# mod_panel_voltage.net
KiCad netlist of a schematic drawn in EAGLE
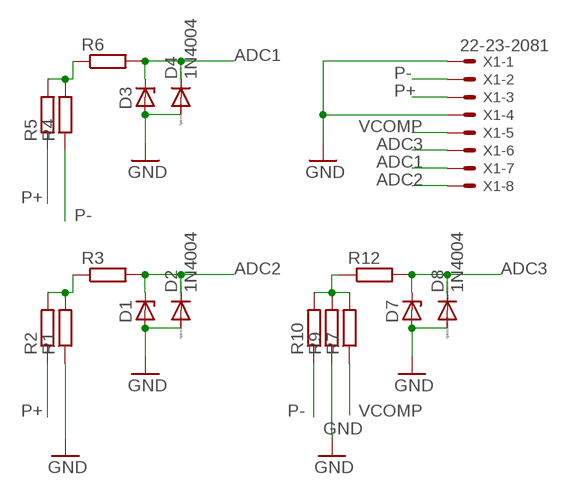
[diagram p0: schematic, sheet 1]

(export (version "E")
  (design (tool "Eeschema 10.0.6"))
  (components
    (comp (ref "D1")
      (value "ZENER-DIODEDO34-7")
      (footprint "eagle-import:DO34Z7")
      (libsource (lib "eagle-import") (part "ZENER-DIODEDO34-7"))
    )
    (comp (ref "D2")
      (value "1N4004")
      (footprint "eagle-import:DO41-10")
      (libsource (lib "eagle-import") (part "1N4004"))
    )
    (comp (ref "D3")
      (value "ZENER-DIODEDO34-7")
      (footprint "eagle-import:DO34Z7")
      (libsource (lib "eagle-import") (part "ZENER-DIODEDO34-7"))
    )
    (comp (ref "D4")
      (value "1N4004")
      (footprint "eagle-import:DO41-10")
      (libsource (lib "eagle-import") (part "1N4004"))
    )
    (comp (ref "D7")
      (value "ZENER-DIODEDO34-7")
      (footprint "eagle-import:DO34Z7")
      (libsource (lib "eagle-import") (part "ZENER-DIODEDO34-7"))
    )
    (comp (ref "D8")
      (value "1N4004")
      (footprint "eagle-import:DO41-10")
      (libsource (lib "eagle-import") (part "1N4004"))
    )
    (comp (ref "R1")
      (value "R-EU_0204/5")
      (footprint "eagle-import:0204_5")
      (libsource (lib "eagle-import") (part "R-EU_0204/5"))
    )
    (comp (ref "R2")
      (value "R-EU_0204/5")
      (footprint "eagle-import:0204_5")
      (libsource (lib "eagle-import") (part "R-EU_0204/5"))
    )
    (comp (ref "R3")
      (value "R-EU_0204/5")
      (footprint "eagle-import:0204_5")
      (libsource (lib "eagle-import") (part "R-EU_0204/5"))
    )
    (comp (ref "R4")
      (value "R-EU_0204/5")
      (footprint "eagle-import:0204_5")
      (libsource (lib "eagle-import") (part "R-EU_0204/5"))
    )
    (comp (ref "R5")
      (value "R-EU_0204/5")
      (footprint "eagle-import:0204_5")
      (libsource (lib "eagle-import") (part "R-EU_0204/5"))
    )
    (comp (ref "R6")
      (value "R-EU_0204/5")
      (footprint "eagle-import:0204_5")
      (libsource (lib "eagle-import") (part "R-EU_0204/5"))
    )
    (comp (ref "R7")
      (value "R-EU_0204/5")
      (footprint "eagle-import:0204_5")
      (libsource (lib "eagle-import") (part "R-EU_0204/5"))
    )
    (comp (ref "R9")
      (value "R-EU_0204/5")
      (footprint "eagle-import:0204_5")
      (libsource (lib "eagle-import") (part "R-EU_0204/5"))
    )
    (comp (ref "R10")
      (value "R-EU_0204/5")
      (footprint "eagle-import:0204_5")
      (libsource (lib "eagle-import") (part "R-EU_0204/5"))
    )
    (comp (ref "R12")
      (value "R-EU_0204/5")
      (footprint "eagle-import:0204_5")
      (libsource (lib "eagle-import") (part "R-EU_0204/5"))
    )
    (comp (ref "X1")
      (value "22-23-2081")
      (footprint "eagle-import:22-23-2081")
      (fields (field (name "MF") "MOLEX"))
      (libsource (lib "eagle-import") (part "22-23-2081"))
    )
  )
  (nets
    (net (code "1") (name "/ADC1") (class "Default")
      (node (ref "D3") (pin "C") (pinfunction "C_C") (pintype "passive"))
      (node (ref "D4") (pin "C") (pinfunction "C_C") (pintype "passive"))
      (node (ref "R6") (pin "2") (pinfunction "2_2") (pintype "passive"))
      (node (ref "X1") (pin "7") (pinfunction "S_7") (pintype "passive"))
    )
    (net (code "2") (name "/ADC2") (class "Default")
      (node (ref "D1") (pin "C") (pinfunction "C_C") (pintype "passive"))
      (node (ref "D2") (pin "C") (pinfunction "C_C") (pintype "passive"))
      (node (ref "R3") (pin "2") (pinfunction "2_2") (pintype "passive"))
      (node (ref "X1") (pin "8") (pinfunction "S_8") (pintype "passive"))
    )
    (net (code "3") (name "/ADC3") (class "Default")
      (node (ref "D7") (pin "C") (pinfunction "C_C") (pintype "passive"))
      (node (ref "D8") (pin "C") (pinfunction "C_C") (pintype "passive"))
      (node (ref "R12") (pin "2") (pinfunction "2_2") (pintype "passive"))
      (node (ref "X1") (pin "6") (pinfunction "S_6") (pintype "passive"))
    )
    (net (code "4") (name "/P+") (class "Default")
      (node (ref "R2") (pin "1") (pinfunction "1_1") (pintype "passive"))
      (node (ref "R5") (pin "1") (pinfunction "1_1") (pintype "passive"))
      (node (ref "X1") (pin "3") (pinfunction "S_3") (pintype "passive"))
    )
    (net (code "5") (name "/P-") (class "Default")
      (node (ref "R10") (pin "1") (pinfunction "1_1") (pintype "passive"))
      (node (ref "R4") (pin "1") (pinfunction "1_1") (pintype "passive"))
      (node (ref "X1") (pin "2") (pinfunction "S_2") (pintype "passive"))
    )
    (net (code "6") (name "/VCOMP") (class "Default")
      (node (ref "R7") (pin "1") (pinfunction "1_1") (pintype "passive"))
      (node (ref "X1") (pin "5") (pinfunction "S_5") (pintype "passive"))
    )
    (net (code "7") (name "GND") (class "Default")
      (node (ref "D1") (pin "A") (pinfunction "A_A") (pintype "passive"))
      (node (ref "D2") (pin "A") (pinfunction "A_A") (pintype "passive"))
      (node (ref "D3") (pin "A") (pinfunction "A_A") (pintype "passive"))
      (node (ref "D4") (pin "A") (pinfunction "A_A") (pintype "passive"))
      (node (ref "D7") (pin "A") (pinfunction "A_A") (pintype "passive"))
      (node (ref "D8") (pin "A") (pinfunction "A_A") (pintype "passive"))
      (node (ref "R1") (pin "1") (pinfunction "1_1") (pintype "passive"))
      (node (ref "R9") (pin "1") (pinfunction "1_1") (pintype "passive"))
      (node (ref "X1") (pin "1") (pinfunction "S_1") (pintype "passive"))
      (node (ref "X1") (pin "4") (pinfunction "S_4") (pintype "passive"))
    )
    (net (code "8") (name "Net-(R1-Pad2)") (class "Default")
      (node (ref "R1") (pin "2") (pinfunction "2_2") (pintype "passive"))
      (node (ref "R2") (pin "2") (pinfunction "2_2") (pintype "passive"))
      (node (ref "R3") (pin "1") (pinfunction "1_1") (pintype "passive"))
    )
    (net (code "9") (name "Net-(R4-Pad2)") (class "Default")
      (node (ref "R4") (pin "2") (pinfunction "2_2") (pintype "passive"))
      (node (ref "R5") (pin "2") (pinfunction "2_2") (pintype "passive"))
      (node (ref "R6") (pin "1") (pinfunction "1_1") (pintype "passive"))
    )
    (net (code "10") (name "Net-(R10-Pad2)") (class "Default")
      (node (ref "R10") (pin "2") (pinfunction "2_2") (pintype "passive"))
      (node (ref "R12") (pin "1") (pinfunction "1_1") (pintype "passive"))
      (node (ref "R7") (pin "2") (pinfunction "2_2") (pintype "passive"))
      (node (ref "R9") (pin "2") (pinfunction "2_2") (pintype "passive"))
    )
  )
)
